# DRV8701.net
KiCad netlist of a schematic drawn in EasyEDA Pro
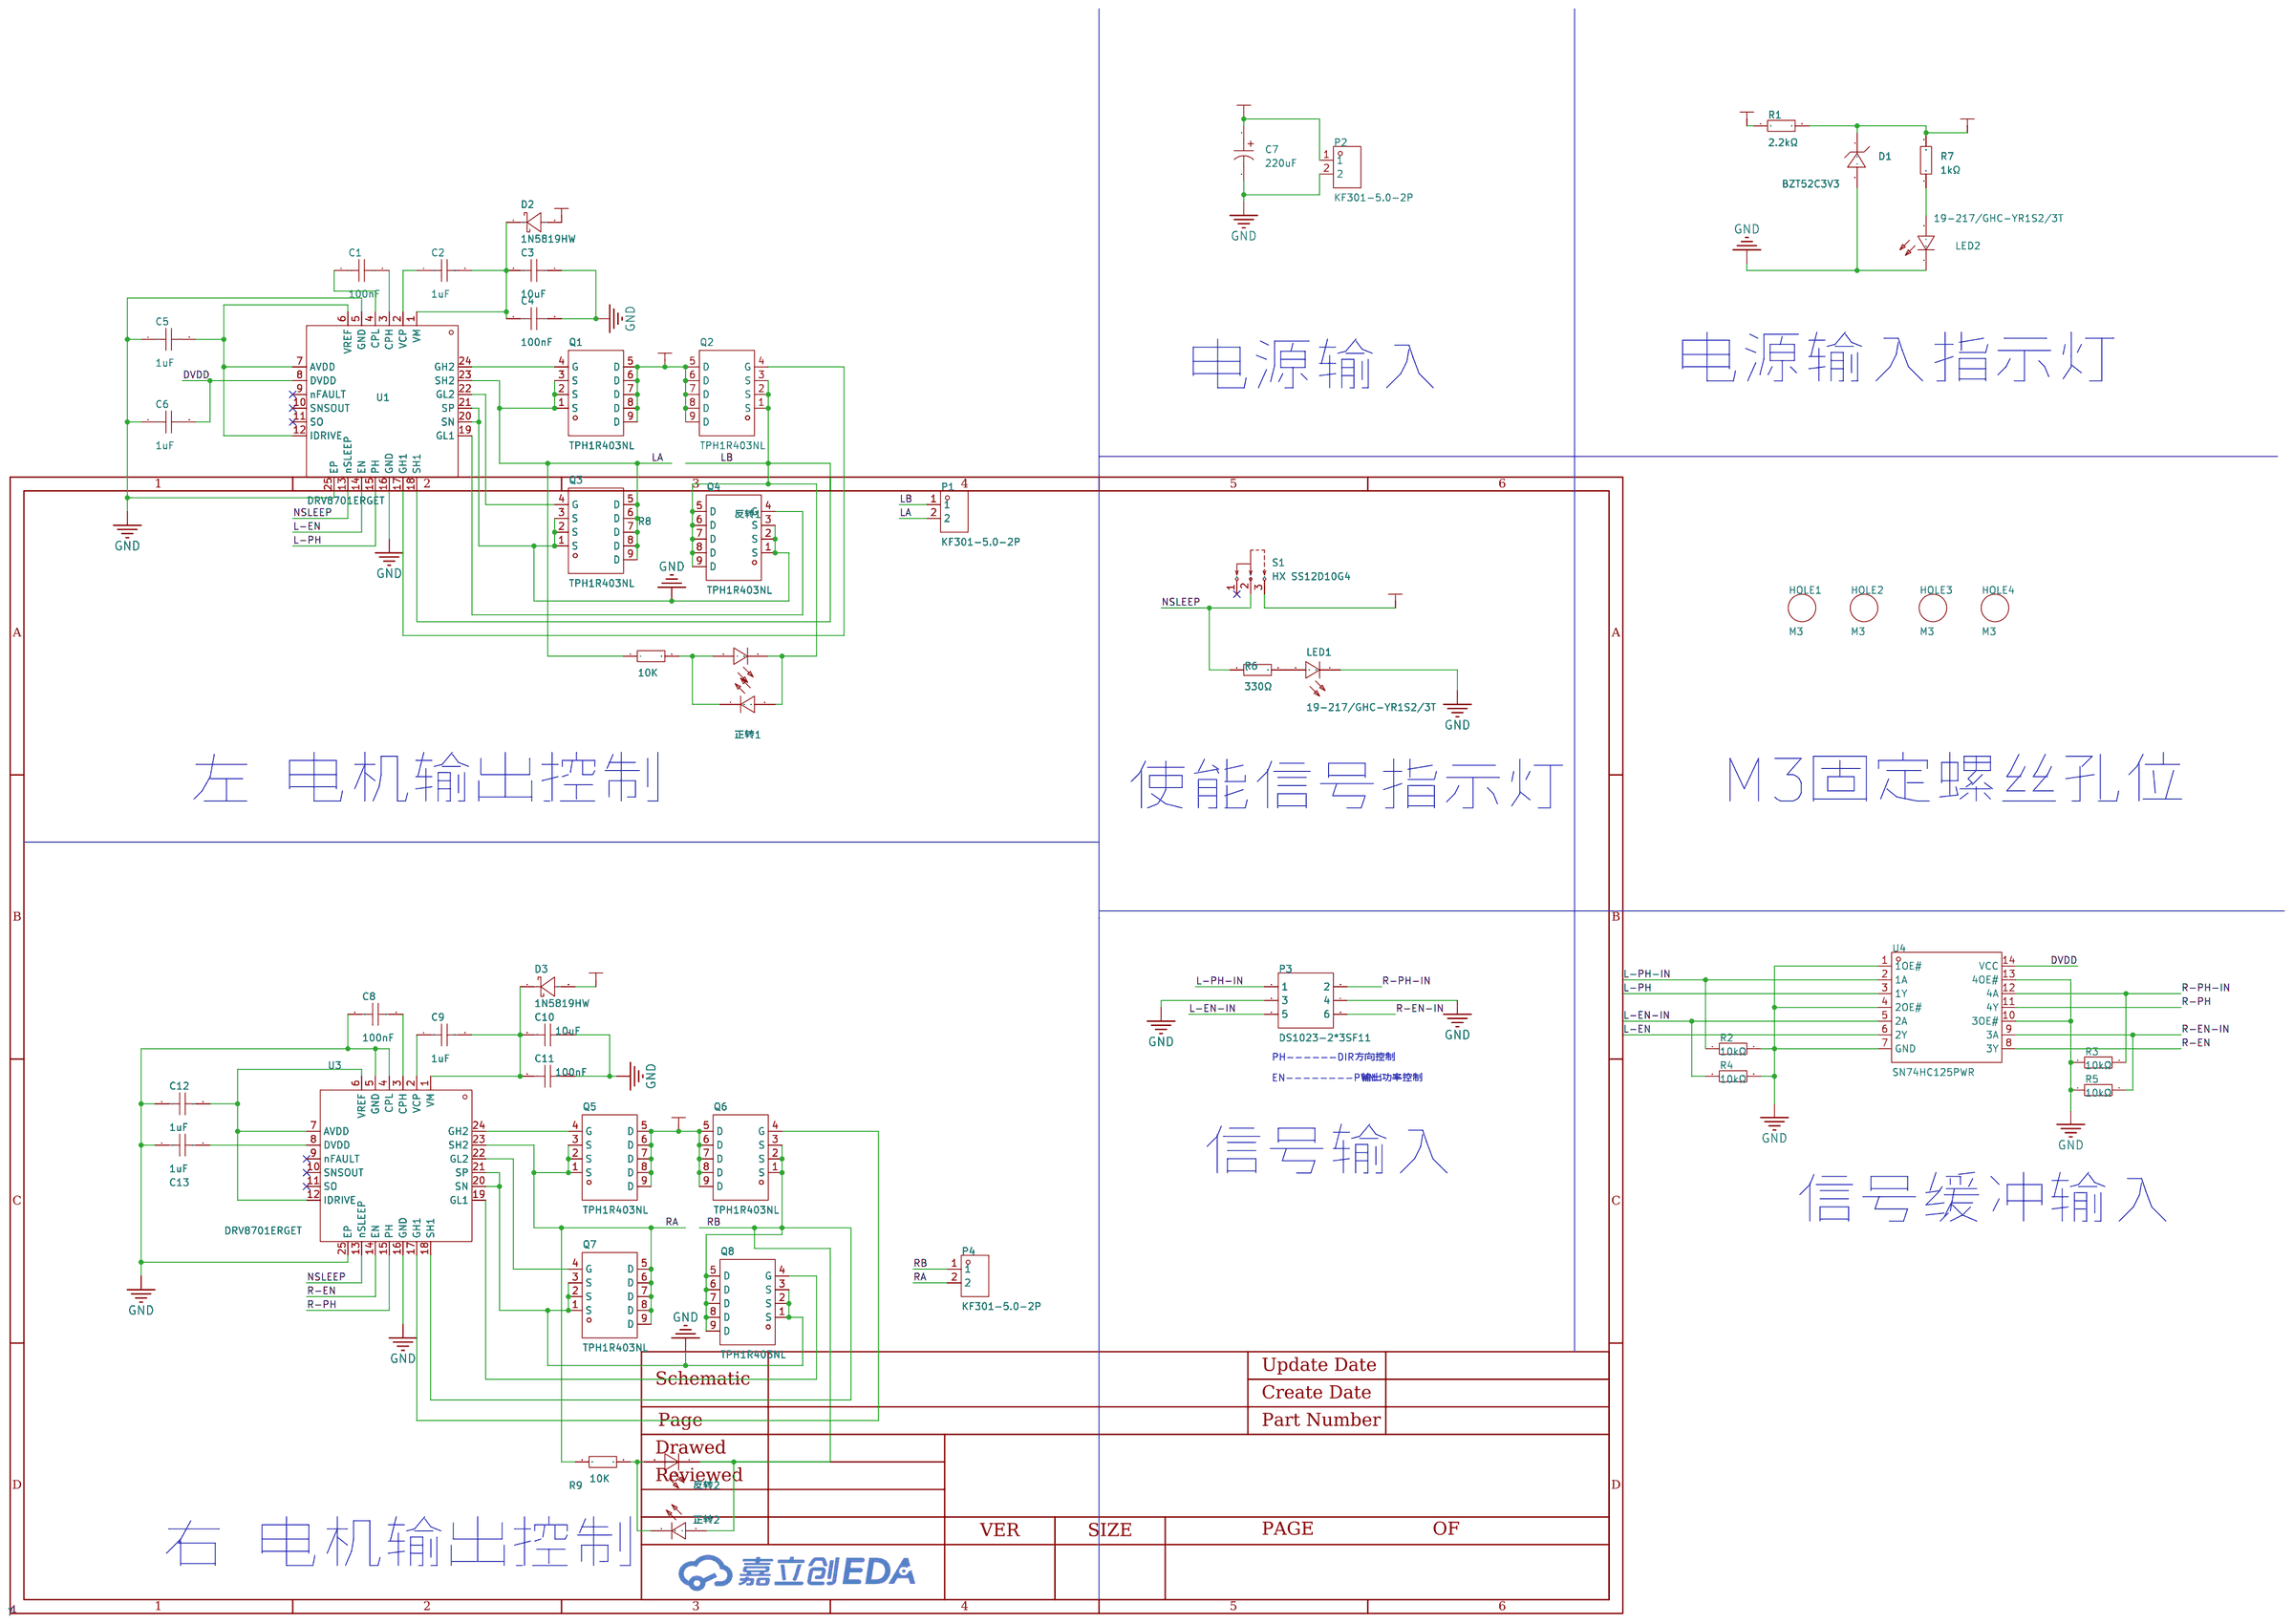
[diagram p0: schematic sheet]

(export (version "E")
  (design (tool "Eeschema 10.0.6"))
  (components
    (comp (ref "C1")
      (value "100nF")
      (footprint "easyedapro:C0603")
      (description "容值:100nF;精度:±10%;额定电压:16V;材质(温度系数):X7R;")
      (fields
        (field (name "Manufacturer Part") "LD03YC104KAB2A\\500")
        (field (name "Manufacturer") "Kyocera AVX")
      )
      (libsource (lib "easyedapro") (part "LD03YC104KAB2A{backslash}500"))
    )
    (comp (ref "C2")
      (value "1uF")
      (footprint "easyedapro:C0603")
      (fields
        (field (name "Manufacturer Part") "JMK063ABJ105MP-F")
        (field (name "Manufacturer") "TAIYO YUDEN(太诱)")
      )
      (libsource (lib "easyedapro") (part "YH-36P-贴片电容"))
    )
    (comp (ref "C3")
      (value "10uF")
      (footprint "easyedapro:C0603")
      (description "容值:10uF;精度:±20%;额定电压:16V;材质(温度系数):-;")
      (fields (field (name "Manufacturer") "SAMSUNG(三星)"))
      (libsource (lib "easyedapro") (part "10UF"))
    )
    (comp (ref "C4")
      (value "100nF")
      (footprint "easyedapro:C0603")
      (description "容值:100nF;精度:±10%;额定电压:16V;材质(温度系数):X7R;")
      (fields
        (field (name "Manufacturer Part") "LD03YC104KAB2A\\500")
        (field (name "Manufacturer") "Kyocera AVX")
      )
      (libsource (lib "easyedapro") (part "LD03YC104KAB2A{backslash}500"))
    )
    (comp (ref "C5")
      (value "1uF")
      (footprint "easyedapro:C0603")
      (fields
        (field (name "Manufacturer Part") "JMK063ABJ105MP-F")
        (field (name "Manufacturer") "TAIYO YUDEN(太诱)")
      )
      (libsource (lib "easyedapro") (part "YH-36P-贴片电容"))
    )
    (comp (ref "C6")
      (value "1uF")
      (footprint "easyedapro:C0603")
      (fields
        (field (name "Manufacturer Part") "JMK063ABJ105MP-F")
        (field (name "Manufacturer") "TAIYO YUDEN(太诱)")
      )
      (libsource (lib "easyedapro") (part "YH-36P-贴片电容"))
    )
    (comp (ref "C7")
      (value "220uF")
      (footprint "easyedapro:CAP-TH_BD6.3-P2.50-D0.5-FD")
      (fields
        (field (name "Manufacturer Part") "25YXJ220M6.3X11")
        (field (name "Manufacturer") "rubycon(红宝石)")
      )
      (libsource (lib "easyedapro") (part "220UF±20%25V 6.3*11 2.5MM"))
    )
    (comp (ref "C8")
      (value "100nF")
      (footprint "easyedapro:C0603")
      (description "容值:100nF;精度:±10%;额定电压:16V;材质(温度系数):X7R;")
      (fields
        (field (name "Manufacturer Part") "LD03YC104KAB2A\\500")
        (field (name "Manufacturer") "Kyocera AVX")
      )
      (libsource (lib "easyedapro") (part "LD03YC104KAB2A{backslash}500"))
    )
    (comp (ref "C9")
      (value "1uF")
      (footprint "easyedapro:C0603")
      (fields
        (field (name "Manufacturer Part") "JMK063ABJ105MP-F")
        (field (name "Manufacturer") "TAIYO YUDEN(太诱)")
      )
      (libsource (lib "easyedapro") (part "YH-36P-贴片电容"))
    )
    (comp (ref "C10")
      (value "10uF")
      (footprint "easyedapro:C0603")
      (description "容值:10uF;精度:±20%;额定电压:16V;材质(温度系数):-;")
      (fields (field (name "Manufacturer") "SAMSUNG(三星)"))
      (libsource (lib "easyedapro") (part "10UF"))
    )
    (comp (ref "C11")
      (value "100nF")
      (footprint "easyedapro:C0603")
      (description "容值:100nF;精度:±10%;额定电压:16V;材质(温度系数):X7R;")
      (fields
        (field (name "Manufacturer Part") "LD03YC104KAB2A\\500")
        (field (name "Manufacturer") "Kyocera AVX")
      )
      (libsource (lib "easyedapro") (part "LD03YC104KAB2A{backslash}500"))
    )
    (comp (ref "C12")
      (value "1uF")
      (footprint "easyedapro:C0603")
      (fields
        (field (name "Manufacturer Part") "JMK063ABJ105MP-F")
        (field (name "Manufacturer") "TAIYO YUDEN(太诱)")
      )
      (libsource (lib "easyedapro") (part "YH-36P-贴片电容"))
    )
    (comp (ref "C13")
      (value "1uF")
      (footprint "easyedapro:C0603")
      (fields
        (field (name "Manufacturer Part") "JMK063ABJ105MP-F")
        (field (name "Manufacturer") "TAIYO YUDEN(太诱)")
      )
      (libsource (lib "easyedapro") (part "YH-36P-贴片电容"))
    )
    (comp (ref "D1")
      (value "BZT52C3V3")
      (footprint "easyedapro:SOD-123_L2.8-W1.8-LS3.7-RD")
      (description "二极管配置:独立式;稳压值(标称值):3.3V;稳压值(范围):3.1V~3.5V;精度:-;功率:350mW;反向电流(Ir):5uA@1V;阻抗(Zzt):95Ω;")
      (fields (field (name "Manufacturer") "CJ(江苏长电/长晶)"))
      (libsource (lib "easyedapro") (part "BZT52C3V3_C2112"))
    )
    (comp (ref "D2")
      (value "1N5819HW")
      (footprint "easyedapro:SOD-123_L2.7-W1.6-LS3.7-RD-1")
      (description "二极管配置:-;直流反向耐压(Vr):40V;平均整流电流(Io):1A;正向压降(Vf):900mV@3A;反向电流(Ir):1mA@40V;")
      (fields (field (name "Manufacturer") "TECH PUBLIC(台舟)"))
      (libsource (lib "easyedapro") (part "1N5819HW"))
    )
    (comp (ref "D3")
      (value "1N5819HW")
      (footprint "easyedapro:SOD-123_L2.7-W1.6-LS3.7-RD-1")
      (description "二极管配置:-;直流反向耐压(Vr):40V;平均整流电流(Io):1A;正向压降(Vf):900mV@3A;反向电流(Ir):1mA@40V;")
      (fields (field (name "Manufacturer") "TECH PUBLIC(台舟)"))
      (libsource (lib "easyedapro") (part "1N5819HW"))
    )
    (comp (ref "HOLE1")
      (value "M3")
      (footprint "easyedapro:M3 5.4MM")
      (libsource (lib "easyedapro") (part "M3"))
    )
    (comp (ref "HOLE2")
      (value "M3")
      (footprint "easyedapro:M3 5.4MM")
      (libsource (lib "easyedapro") (part "M3"))
    )
    (comp (ref "HOLE3")
      (value "M3")
      (footprint "easyedapro:M3 5.4MM")
      (libsource (lib "easyedapro") (part "M3"))
    )
    (comp (ref "HOLE4")
      (value "M3")
      (footprint "easyedapro:M3 5.4MM")
      (libsource (lib "easyedapro") (part "M3"))
    )
    (comp (ref "LED1")
      (value "19-217/GHC-YR1S2/3T")
      (footprint "easyedapro:LED0603-RD")
      (description "发光颜色:翠绿;二极管配置:-;主波长:520nm~535nm;色温:-;功率:110mW;安装方式:-;")
      (fields (field (name "Manufacturer") "EVERLIGHT(亿光)"))
      (libsource (lib "easyedapro") (part "19-217/GHC-YR1S2/3T"))
    )
    (comp (ref "LED2")
      (value "19-217/GHC-YR1S2/3T")
      (footprint "easyedapro:LED0603-RD")
      (description "发光颜色:翠绿;二极管配置:-;主波长:520nm~535nm;色温:-;功率:110mW;安装方式:-;")
      (fields (field (name "Manufacturer") "EVERLIGHT(亿光)"))
      (libsource (lib "easyedapro") (part "19-217/GHC-YR1S2/3T"))
    )
    (comp (ref "P1")
      (value "KF301-5.0-2P")
      (footprint "easyedapro:CONN-TH_P5.00_KF301-5.0-2P")
      (fields (field (name "Manufacturer") "KEFA(科发)"))
      (libsource (lib "easyedapro") (part "KF301-5.0-2P"))
    )
    (comp (ref "P2")
      (value "KF301-5.0-2P")
      (footprint "easyedapro:CONN-TH_P5.00_KF301-5.0-2P")
      (fields (field (name "Manufacturer") "KEFA(科发)"))
      (libsource (lib "easyedapro") (part "KF301-5.0-2P"))
    )
    (comp (ref "P3")
      (value "DS1023-2*3SF11")
      (footprint "easyedapro:HDR-TH_6P-P2.54-V-F-R2-C3-S2.54")
      (description "排数:双排;总孔位数:6;间距:2.54mm;插孔结构:2x3P;行距:2.54mm;安装类型:直插;塑高:-;触头材质:-;触头镀层:-;")
      (fields (field (name "Manufacturer") "CONNFLY"))
      (libsource (lib "easyedapro") (part "Header-Female-2.54_2x3"))
    )
    (comp (ref "P4")
      (value "KF301-5.0-2P")
      (footprint "easyedapro:CONN-TH_P5.00_KF301-5.0-2P")
      (fields (field (name "Manufacturer") "KEFA(科发)"))
      (libsource (lib "easyedapro") (part "KF301-5.0-2P"))
    )
    (comp (ref "Q1")
      (value "TPH1R403NL")
      (footprint "easyedapro:DSOP-8_L5.0-W5.0-P1.27-LS6.0-BL-EP")
      (fields (field (name "Manufacturer") "TOSHIBA(东芝)"))
      (libsource (lib "easyedapro") (part "TPH1R403NL"))
    )
    (comp (ref "Q2")
      (value "TPH1R403NL")
      (footprint "easyedapro:DSOP-8_L5.0-W5.0-P1.27-LS6.0-BL-EP")
      (fields (field (name "Manufacturer") "TOSHIBA(东芝)"))
      (libsource (lib "easyedapro") (part "TPH1R403NL"))
    )
    (comp (ref "Q3")
      (value "TPH1R403NL")
      (footprint "easyedapro:DSOP-8_L5.0-W5.0-P1.27-LS6.0-BL-EP")
      (fields (field (name "Manufacturer") "TOSHIBA(东芝)"))
      (libsource (lib "easyedapro") (part "TPH1R403NL"))
    )
    (comp (ref "Q4")
      (value "TPH1R403NL")
      (footprint "easyedapro:DSOP-8_L5.0-W5.0-P1.27-LS6.0-BL-EP")
      (fields (field (name "Manufacturer") "TOSHIBA(东芝)"))
      (libsource (lib "easyedapro") (part "TPH1R403NL"))
    )
    (comp (ref "Q5")
      (value "TPH1R403NL")
      (footprint "easyedapro:DSOP-8_L5.0-W5.0-P1.27-LS6.0-BL-EP")
      (fields (field (name "Manufacturer") "TOSHIBA(东芝)"))
      (libsource (lib "easyedapro") (part "TPH1R403NL"))
    )
    (comp (ref "Q6")
      (value "TPH1R403NL")
      (footprint "easyedapro:DSOP-8_L5.0-W5.0-P1.27-LS6.0-BL-EP")
      (fields (field (name "Manufacturer") "TOSHIBA(东芝)"))
      (libsource (lib "easyedapro") (part "TPH1R403NL"))
    )
    (comp (ref "Q7")
      (value "TPH1R403NL")
      (footprint "easyedapro:DSOP-8_L5.0-W5.0-P1.27-LS6.0-BL-EP")
      (fields (field (name "Manufacturer") "TOSHIBA(东芝)"))
      (libsource (lib "easyedapro") (part "TPH1R403NL"))
    )
    (comp (ref "Q8")
      (value "TPH1R403NL")
      (footprint "easyedapro:DSOP-8_L5.0-W5.0-P1.27-LS6.0-BL-EP")
      (fields (field (name "Manufacturer") "TOSHIBA(东芝)"))
      (libsource (lib "easyedapro") (part "TPH1R403NL"))
    )
    (comp (ref "R1")
      (value "2.2kΩ")
      (footprint "easyedapro:R0805")
      (description "电阻类型:厚膜电阻;阻值:2.2kΩ;精度:±5%;功率:125mW;")
      (fields (field (name "Manufacturer Part") "RC0805JR-072K2L") (field (name "Manufacturer") "YAGEO(国巨)"))
      (libsource (lib "easyedapro") (part "RC0805JR-072K2L"))
    )
    (comp (ref "R2")
      (value "10kΩ")
      (footprint "easyedapro:R0603")
      (description "电阻类型:厚膜电阻;阻值:10kΩ;精度:±1%;功率:100mW;")
      (fields (field (name "Manufacturer Part") "AC0603FR-0710KL") (field (name "Manufacturer") "YAGEO(国巨)"))
      (libsource (lib "easyedapro") (part "AC0603FR-0710KL"))
    )
    (comp (ref "R3")
      (value "10kΩ")
      (footprint "easyedapro:R0603")
      (description "电阻类型:厚膜电阻;阻值:10kΩ;精度:±1%;功率:100mW;")
      (fields (field (name "Manufacturer Part") "AC0603FR-0710KL") (field (name "Manufacturer") "YAGEO(国巨)"))
      (libsource (lib "easyedapro") (part "AC0603FR-0710KL"))
    )
    (comp (ref "R4")
      (value "10kΩ")
      (footprint "easyedapro:R0603")
      (description "电阻类型:厚膜电阻;阻值:10kΩ;精度:±1%;功率:100mW;")
      (fields (field (name "Manufacturer Part") "AC0603FR-0710KL") (field (name "Manufacturer") "YAGEO(国巨)"))
      (libsource (lib "easyedapro") (part "AC0603FR-0710KL"))
    )
    (comp (ref "R5")
      (value "10kΩ")
      (footprint "easyedapro:R0603")
      (description "电阻类型:厚膜电阻;阻值:10kΩ;精度:±1%;功率:100mW;")
      (fields (field (name "Manufacturer Part") "AC0603FR-0710KL") (field (name "Manufacturer") "YAGEO(国巨)"))
      (libsource (lib "easyedapro") (part "AC0603FR-0710KL"))
    )
    (comp (ref "R6")
      (value "330Ω")
      (footprint "easyedapro:R0402")
      (description "电阻类型:厚膜电阻;阻值:330Ω;精度:±1%;功率:62.5mW;")
      (fields
        (field (name "Manufacturer Part") "0402WGF3300TCE")
        (field (name "Manufacturer") "UNI-ROYAL(厚声)")
      )
      (libsource (lib "easyedapro") (part "0402WGF3300TCE"))
    )
    (comp (ref "R7")
      (value "1kΩ")
      (footprint "easyedapro:R0603")
      (description "阻值:1kΩ;精度:±5%;功率:100mW;")
      (fields (field (name "Manufacturer Part") "ACD03K102JT") (field (name "Manufacturer") "FH(风华)"))
      (libsource (lib "easyedapro") (part "ACD03K102JT"))
    )
    (comp (ref "R8") (value "10K") (footprint "easyedapro:R0603") (libsource (lib "easyedapro") (part "电阻")))
    (comp (ref "R9") (value "10K") (footprint "easyedapro:R0603") (libsource (lib "easyedapro") (part "电阻")))
    (comp (ref "S1")
      (value "HX SS12D10G4")
      (footprint "easyedapro:SW-TH_SHOU-HAN_SS12D10G4")
      (fields (field (name "Manufacturer") "hanxia(韩下)"))
      (libsource (lib "easyedapro") (part "HX SS12D10G4"))
    )
    (comp (ref "U1")
      (value "DRV8701ERGET")
      (footprint "easyedapro:VQFN-24_L4.0-W4.0-P0.50-BL-EP2.5")
      (description "电源电压:0V~5.5V;输出电流:-;接口:并行;")
      (fields (field (name "Manufacturer") "TI(德州仪器)"))
      (libsource (lib "easyedapro") (part "DRV8701ERGET"))
    )
    (comp (ref "U3")
      (value "DRV8701ERGET")
      (footprint "easyedapro:VQFN-24_L4.0-W4.0-P0.50-BL-EP2.5")
      (description "电源电压:0V~5.5V;输出电流:-;接口:并行;")
      (fields (field (name "Manufacturer") "TI(德州仪器)"))
      (libsource (lib "easyedapro") (part "DRV8701ERGET"))
    )
    (comp (ref "U4")
      (value "SN74HC125PWR")
      (footprint "easyedapro:TSSOP-14_L5.0-W4.4-P0.65-LS6.5-BL")
      (description "类型:缓冲器，非反相;电源电压:2V~6V;输入类型:-;输出类型:三态;低电平输出电流(IOL):7.8mA;高电平输出电流(IOH):7.8mA;工作温度:-40°C~+85°C;")
      (fields (field (name "Manufacturer") "TI(德州仪器)"))
      (libsource (lib "easyedapro") (part "SN74HC125PWR"))
    )
    (comp (ref "反转1")
      (value "19-217/GHC-YR1S2/3T")
      (footprint "easyedapro:LED0603-RD")
      (description "发光颜色:翠绿;二极管配置:-;主波长:520nm~535nm;色温:-;功率:110mW;安装方式:-;")
      (fields (field (name "Manufacturer") "EVERLIGHT(亿光)"))
      (libsource (lib "easyedapro") (part "19-217/GHC-YR1S2/3T"))
    )
    (comp (ref "反转2")
      (value "19-217/GHC-YR1S2/3T")
      (footprint "easyedapro:LED0603-RD")
      (description "发光颜色:翠绿;二极管配置:-;主波长:520nm~535nm;色温:-;功率:110mW;安装方式:-;")
      (fields (field (name "Manufacturer") "EVERLIGHT(亿光)"))
      (libsource (lib "easyedapro") (part "19-217/GHC-YR1S2/3T"))
    )
    (comp (ref "正转1")
      (value "19-217/GHC-YR1S2/3T")
      (footprint "easyedapro:LED0603-RD")
      (description "发光颜色:翠绿;二极管配置:-;主波长:520nm~535nm;色温:-;功率:110mW;安装方式:-;")
      (fields (field (name "Manufacturer") "EVERLIGHT(亿光)"))
      (libsource (lib "easyedapro") (part "19-217/GHC-YR1S2/3T"))
    )
    (comp (ref "正转2")
      (value "19-217/GHC-YR1S2/3T")
      (footprint "easyedapro:LED0603-RD")
      (description "发光颜色:翠绿;二极管配置:-;主波长:520nm~535nm;色温:-;功率:110mW;安装方式:-;")
      (fields (field (name "Manufacturer") "EVERLIGHT(亿光)"))
      (libsource (lib "easyedapro") (part "19-217/GHC-YR1S2/3T"))
    )
  )
  (nets
    (net (code "1") (name "/DVDD") (class "Default")
      (node (ref "C6") (pin "2") (pinfunction "2_2") (pintype "input"))
      (node (ref "U1") (pin "8") (pinfunction "DVDD_8") (pintype "input"))
      (node (ref "U4") (pin "14") (pinfunction "VCC_14") (pintype "input"))
    )
    (net (code "2") (name "/L-EN") (class "Default")
      (node (ref "U1") (pin "14") (pinfunction "EN_14") (pintype "input"))
      (node (ref "U4") (pin "6") (pinfunction "2Y_6") (pintype "input"))
    )
    (net (code "3") (name "/L-EN-IN") (class "Default")
      (node (ref "P3") (pin "5") (pinfunction "5_5") (pintype "input"))
      (node (ref "R4") (pin "1") (pinfunction "1_1") (pintype "input"))
      (node (ref "U4") (pin "5") (pinfunction "2A_5") (pintype "input"))
    )
    (net (code "4") (name "/L-PH") (class "Default")
      (node (ref "U1") (pin "15") (pinfunction "PH_15") (pintype "input"))
      (node (ref "U4") (pin "3") (pinfunction "1Y_3") (pintype "input"))
    )
    (net (code "5") (name "/L-PH-IN") (class "Default")
      (node (ref "P3") (pin "1") (pinfunction "1_1") (pintype "input"))
      (node (ref "R2") (pin "1") (pinfunction "1_1") (pintype "input"))
      (node (ref "U4") (pin "2") (pinfunction "1A_2") (pintype "input"))
    )
    (net (code "6") (name "/LA") (class "Default")
      (node (ref "P1") (pin "2") (pinfunction "2_2") (pintype "input"))
      (node (ref "Q1") (pin "1") (pinfunction "S_1") (pintype "input"))
      (node (ref "Q1") (pin "2") (pinfunction "S_2") (pintype "input"))
      (node (ref "Q1") (pin "3") (pinfunction "S_3") (pintype "input"))
      (node (ref "Q3") (pin "5") (pinfunction "D_5") (pintype "input"))
      (node (ref "Q3") (pin "6") (pinfunction "D_6") (pintype "input"))
      (node (ref "Q3") (pin "7") (pinfunction "D_7") (pintype "input"))
      (node (ref "Q3") (pin "8") (pinfunction "D_8") (pintype "input"))
      (node (ref "Q3") (pin "9") (pinfunction "D_9") (pintype "input"))
      (node (ref "R8") (pin "1") (pinfunction "1_1") (pintype "input"))
      (node (ref "U1") (pin "23") (pinfunction "SH2_23") (pintype "input"))
    )
    (net (code "7") (name "/LB") (class "Default")
      (node (ref "P1") (pin "1") (pinfunction "1_1") (pintype "input"))
      (node (ref "Q2") (pin "1") (pinfunction "S_1") (pintype "input"))
      (node (ref "Q2") (pin "2") (pinfunction "S_2") (pintype "input"))
      (node (ref "Q2") (pin "3") (pinfunction "S_3") (pintype "input"))
      (node (ref "Q4") (pin "5") (pinfunction "D_5") (pintype "input"))
      (node (ref "Q4") (pin "6") (pinfunction "D_6") (pintype "input"))
      (node (ref "Q4") (pin "7") (pinfunction "D_7") (pintype "input"))
      (node (ref "Q4") (pin "8") (pinfunction "D_8") (pintype "input"))
      (node (ref "Q4") (pin "9") (pinfunction "D_9") (pintype "input"))
      (node (ref "U1") (pin "18") (pinfunction "SH1_18") (pintype "input"))
      (node (ref "反转1") (pin "1") (pinfunction "C_1") (pintype "input"))
      (node (ref "正转1") (pin "2") (pinfunction "A_2") (pintype "input"))
    )
    (net (code "8") (name "/NSLEEP") (class "Default")
      (node (ref "R6") (pin "1") (pinfunction "1_1") (pintype "input"))
      (node (ref "S1") (pin "2") (pinfunction "2_2") (pintype "input"))
      (node (ref "U1") (pin "13") (pinfunction "nSLEEP_13") (pintype "input"))
      (node (ref "U3") (pin "13") (pinfunction "nSLEEP_13") (pintype "input"))
    )
    (net (code "9") (name "/R-EN") (class "Default")
      (node (ref "U3") (pin "14") (pinfunction "EN_14") (pintype "input"))
      (node (ref "U4") (pin "8") (pinfunction "3Y_8") (pintype "input"))
    )
    (net (code "10") (name "/R-EN-IN") (class "Default")
      (node (ref "P3") (pin "6") (pinfunction "6_6") (pintype "input"))
      (node (ref "R5") (pin "2") (pinfunction "2_2") (pintype "input"))
      (node (ref "U4") (pin "9") (pinfunction "3A_9") (pintype "input"))
    )
    (net (code "11") (name "/R-PH") (class "Default")
      (node (ref "U3") (pin "15") (pinfunction "PH_15") (pintype "input"))
      (node (ref "U4") (pin "11") (pinfunction "4Y_11") (pintype "input"))
    )
    (net (code "12") (name "/R-PH-IN") (class "Default")
      (node (ref "P3") (pin "2") (pinfunction "2_2") (pintype "input"))
      (node (ref "R3") (pin "2") (pinfunction "2_2") (pintype "input"))
      (node (ref "U4") (pin "12") (pinfunction "4A_12") (pintype "input"))
    )
    (net (code "13") (name "/RA") (class "Default")
      (node (ref "P4") (pin "2") (pinfunction "2_2") (pintype "input"))
      (node (ref "Q5") (pin "1") (pinfunction "S_1") (pintype "input"))
      (node (ref "Q5") (pin "2") (pinfunction "S_2") (pintype "input"))
      (node (ref "Q5") (pin "3") (pinfunction "S_3") (pintype "input"))
      (node (ref "Q7") (pin "5") (pinfunction "D_5") (pintype "input"))
      (node (ref "Q7") (pin "6") (pinfunction "D_6") (pintype "input"))
      (node (ref "Q7") (pin "7") (pinfunction "D_7") (pintype "input"))
      (node (ref "Q7") (pin "8") (pinfunction "D_8") (pintype "input"))
      (node (ref "Q7") (pin "9") (pinfunction "D_9") (pintype "input"))
      (node (ref "R9") (pin "1") (pinfunction "1_1") (pintype "input"))
      (node (ref "U3") (pin "23") (pinfunction "SH2_23") (pintype "input"))
    )
    (net (code "14") (name "/RB") (class "Default")
      (node (ref "P4") (pin "1") (pinfunction "1_1") (pintype "input"))
      (node (ref "Q6") (pin "1") (pinfunction "S_1") (pintype "input"))
      (node (ref "Q6") (pin "2") (pinfunction "S_2") (pintype "input"))
      (node (ref "Q6") (pin "3") (pinfunction "S_3") (pintype "input"))
      (node (ref "Q8") (pin "5") (pinfunction "D_5") (pintype "input"))
      (node (ref "Q8") (pin "6") (pinfunction "D_6") (pintype "input"))
      (node (ref "Q8") (pin "7") (pinfunction "D_7") (pintype "input"))
      (node (ref "Q8") (pin "8") (pinfunction "D_8") (pintype "input"))
      (node (ref "Q8") (pin "9") (pinfunction "D_9") (pintype "input"))
      (node (ref "U3") (pin "18") (pinfunction "SH1_18") (pintype "input"))
      (node (ref "反转2") (pin "1") (pinfunction "C_1") (pintype "input"))
      (node (ref "正转2") (pin "2") (pinfunction "A_2") (pintype "input"))
    )
    (net (code "15") (name "3V3") (class "Default")
      (node (ref "D1") (pin "1") (pinfunction "K_1") (pintype "input"))
      (node (ref "R1") (pin "2") (pinfunction "2_2") (pintype "input"))
      (node (ref "R7") (pin "2") (pinfunction "2_2") (pintype "input"))
      (node (ref "S1") (pin "3") (pinfunction "3_3") (pintype "input"))
    )
    (net (code "16") (name "GND") (class "Default")
      (node (ref "C10") (pin "1") (pinfunction "1_1") (pintype "input"))
      (node (ref "C11") (pin "2") (pinfunction "2_2") (pintype "input"))
      (node (ref "C12") (pin "1") (pinfunction "1_1") (pintype "input"))
      (node (ref "C13") (pin "1") (pinfunction "1_1") (pintype "input"))
      (node (ref "C3") (pin "1") (pinfunction "1_1") (pintype "input"))
      (node (ref "C4") (pin "2") (pinfunction "2_2") (pintype "input"))
      (node (ref "C5") (pin "1") (pinfunction "1_1") (pintype "input"))
      (node (ref "C6") (pin "1") (pinfunction "1_1") (pintype "input"))
      (node (ref "C7") (pin "2") (pinfunction "2_2") (pintype "input"))
      (node (ref "C8") (pin "1") (pinfunction "1_1") (pintype "input"))
      (node (ref "D1") (pin "2") (pinfunction "A_2") (pintype "input"))
      (node (ref "LED1") (pin "1") (pinfunction "C_1") (pintype "input"))
      (node (ref "LED2") (pin "1") (pinfunction "C_1") (pintype "input"))
      (node (ref "P2") (pin "2") (pinfunction "2_2") (pintype "input"))
      (node (ref "P3") (pin "3") (pinfunction "3_3") (pintype "input"))
      (node (ref "P3") (pin "4") (pinfunction "4_4") (pintype "input"))
      (node (ref "Q3") (pin "1") (pinfunction "S_1") (pintype "input"))
      (node (ref "Q3") (pin "2") (pinfunction "S_2") (pintype "input"))
      (node (ref "Q3") (pin "3") (pinfunction "S_3") (pintype "input"))
      (node (ref "Q4") (pin "1") (pinfunction "S_1") (pintype "input"))
      (node (ref "Q4") (pin "2") (pinfunction "S_2") (pintype "input"))
      (node (ref "Q4") (pin "3") (pinfunction "S_3") (pintype "input"))
      (node (ref "Q7") (pin "1") (pinfunction "S_1") (pintype "input"))
      (node (ref "Q7") (pin "2") (pinfunction "S_2") (pintype "input"))
      (node (ref "Q7") (pin "3") (pinfunction "S_3") (pintype "input"))
      (node (ref "Q8") (pin "1") (pinfunction "S_1") (pintype "input"))
      (node (ref "Q8") (pin "2") (pinfunction "S_2") (pintype "input"))
      (node (ref "Q8") (pin "3") (pinfunction "S_3") (pintype "input"))
      (node (ref "R2") (pin "2") (pinfunction "2_2") (pintype "input"))
      (node (ref "R3") (pin "1") (pinfunction "1_1") (pintype "input"))
      (node (ref "R4") (pin "2") (pinfunction "2_2") (pintype "input"))
      (node (ref "R5") (pin "1") (pinfunction "1_1") (pintype "input"))
      (node (ref "U1") (pin "16") (pinfunction "GND_16") (pintype "input"))
      (node (ref "U1") (pin "20") (pinfunction "SN_20") (pintype "input"))
      (node (ref "U1") (pin "21") (pinfunction "SP_21") (pintype "input"))
      (node (ref "U1") (pin "25") (pinfunction "EP_25") (pintype "input"))
      (node (ref "U1") (pin "5") (pinfunction "GND_5") (pintype "input"))
      (node (ref "U3") (pin "16") (pinfunction "GND_16") (pintype "input"))
      (node (ref "U3") (pin "20") (pinfunction "SN_20") (pintype "input"))
      (node (ref "U3") (pin "21") (pinfunction "SP_21") (pintype "input"))
      (node (ref "U3") (pin "25") (pinfunction "EP_25") (pintype "input"))
      (node (ref "U3") (pin "4") (pinfunction "CPL_4") (pintype "input"))
      (node (ref "U3") (pin "5") (pinfunction "GND_5") (pintype "input"))
      (node (ref "U4") (pin "1") (pinfunction "1OE#_1") (pintype "input"))
      (node (ref "U4") (pin "10") (pinfunction "3OE#_10") (pintype "input"))
      (node (ref "U4") (pin "13") (pinfunction "4OE#_13") (pintype "input"))
      (node (ref "U4") (pin "4") (pinfunction "2OE#_4") (pintype "input"))
      (node (ref "U4") (pin "7") (pinfunction "GND_7") (pintype "input"))
    )
    (net (code "17") (name "Net-(D2-K)") (class "Default")
      (node (ref "C2") (pin "2") (pinfunction "2_2") (pintype "input"))
      (node (ref "C3") (pin "2") (pinfunction "2_2") (pintype "input"))
      (node (ref "C4") (pin "1") (pinfunction "1_1") (pintype "input"))
      (node (ref "D2") (pin "1") (pinfunction "K_1") (pintype "input"))
      (node (ref "U1") (pin "1") (pinfunction "VM_1") (pintype "input"))
    )
    (net (code "18") (name "Net-(D3-K)") (class "Default")
      (node (ref "C10") (pin "2") (pinfunction "2_2") (pintype "input"))
      (node (ref "C11") (pin "1") (pinfunction "1_1") (pintype "input"))
      (node (ref "C9") (pin "2") (pinfunction "2_2") (pintype "input"))
      (node (ref "D3") (pin "1") (pinfunction "K_1") (pintype "input"))
      (node (ref "U3") (pin "1") (pinfunction "VM_1") (pintype "input"))
    )
    (net (code "19") (name "Net-(LED1-A)") (class "Default")
      (node (ref "LED1") (pin "2") (pinfunction "A_2") (pintype "input"))
      (node (ref "R6") (pin "2") (pinfunction "2_2") (pintype "input"))
    )
    (net (code "20") (name "Net-(LED2-A)") (class "Default")
      (node (ref "LED2") (pin "2") (pinfunction "A_2") (pintype "input"))
      (node (ref "R7") (pin "1") (pinfunction "1_1") (pintype "input"))
    )
    (net (code "21") (name "Net-(Q1-G)") (class "Default")
      (node (ref "Q1") (pin "4") (pinfunction "G_4") (pintype "input"))
      (node (ref "U1") (pin "24") (pinfunction "GH2_24") (pintype "input"))
    )
    (net (code "22") (name "Net-(Q2-G)") (class "Default")
      (node (ref "Q2") (pin "4") (pinfunction "G_4") (pintype "input"))
      (node (ref "U1") (pin "17") (pinfunction "GH1_17") (pintype "input"))
    )
    (net (code "23") (name "Net-(Q3-G)") (class "Default")
      (node (ref "Q3") (pin "4") (pinfunction "G_4") (pintype "input"))
      (node (ref "U1") (pin "22") (pinfunction "GL2_22") (pintype "input"))
    )
    (net (code "24") (name "Net-(Q4-G)") (class "Default")
      (node (ref "Q4") (pin "4") (pinfunction "G_4") (pintype "input"))
      (node (ref "U1") (pin "19") (pinfunction "GL1_19") (pintype "input"))
    )
    (net (code "25") (name "Net-(Q5-G)") (class "Default")
      (node (ref "Q5") (pin "4") (pinfunction "G_4") (pintype "input"))
      (node (ref "U3") (pin "24") (pinfunction "GH2_24") (pintype "input"))
    )
    (net (code "26") (name "Net-(Q6-G)") (class "Default")
      (node (ref "Q6") (pin "4") (pinfunction "G_4") (pintype "input"))
      (node (ref "U3") (pin "17") (pinfunction "GH1_17") (pintype "input"))
    )
    (net (code "27") (name "Net-(Q7-G)") (class "Default")
      (node (ref "Q7") (pin "4") (pinfunction "G_4") (pintype "input"))
      (node (ref "U3") (pin "22") (pinfunction "GL2_22") (pintype "input"))
    )
    (net (code "28") (name "Net-(Q8-G)") (class "Default")
      (node (ref "Q8") (pin "4") (pinfunction "G_4") (pintype "input"))
      (node (ref "U3") (pin "19") (pinfunction "GL1_19") (pintype "input"))
    )
    (net (code "29") (name "Net-(U1-AVDD)") (class "Default")
      (node (ref "C5") (pin "2") (pinfunction "2_2") (pintype "input"))
      (node (ref "U1") (pin "12") (pinfunction "IDRIVE_12") (pintype "input"))
      (node (ref "U1") (pin "6") (pinfunction "VREF_6") (pintype "input"))
      (node (ref "U1") (pin "7") (pinfunction "AVDD_7") (pintype "input"))
    )
    (net (code "30") (name "Net-(U1-CPH)") (class "Default")
      (node (ref "C1") (pin "2") (pinfunction "2_2") (pintype "input"))
      (node (ref "U1") (pin "3") (pinfunction "CPH_3") (pintype "input"))
    )
    (net (code "31") (name "Net-(U1-CPL)") (class "Default")
      (node (ref "C1") (pin "1") (pinfunction "1_1") (pintype "input"))
      (node (ref "U1") (pin "4") (pinfunction "CPL_4") (pintype "input"))
    )
    (net (code "32") (name "Net-(U1-VCP)") (class "Default")
      (node (ref "C2") (pin "1") (pinfunction "1_1") (pintype "input"))
      (node (ref "U1") (pin "2") (pinfunction "VCP_2") (pintype "input"))
    )
    (net (code "33") (name "Net-(U3-AVDD)") (class "Default")
      (node (ref "C12") (pin "2") (pinfunction "2_2") (pintype "input"))
      (node (ref "U3") (pin "12") (pinfunction "IDRIVE_12") (pintype "input"))
      (node (ref "U3") (pin "6") (pinfunction "VREF_6") (pintype "input"))
      (node (ref "U3") (pin "7") (pinfunction "AVDD_7") (pintype "input"))
    )
    (net (code "34") (name "Net-(U3-CPH)") (class "Default")
      (node (ref "C8") (pin "2") (pinfunction "2_2") (pintype "input"))
      (node (ref "U3") (pin "3") (pinfunction "CPH_3") (pintype "input"))
    )
    (net (code "35") (name "Net-(U3-DVDD)") (class "Default")
      (node (ref "C13") (pin "2") (pinfunction "2_2") (pintype "input"))
      (node (ref "U3") (pin "8") (pinfunction "DVDD_8") (pintype "input"))
    )
    (net (code "36") (name "Net-(U3-VCP)") (class "Default")
      (node (ref "C9") (pin "1") (pinfunction "1_1") (pintype "input"))
      (node (ref "U3") (pin "2") (pinfunction "VCP_2") (pintype "input"))
    )
    (net (code "37") (name "Net-(反转1-A)") (class "Default")
      (node (ref "R8") (pin "2") (pinfunction "2_2") (pintype "input"))
      (node (ref "反转1") (pin "2") (pinfunction "A_2") (pintype "input"))
      (node (ref "正转1") (pin "1") (pinfunction "C_1") (pintype "input"))
    )
    (net (code "38") (name "Net-(反转2-A)") (class "Default")
      (node (ref "R9") (pin "2") (pinfunction "2_2") (pintype "input"))
      (node (ref "反转2") (pin "2") (pinfunction "A_2") (pintype "input"))
      (node (ref "正转2") (pin "1") (pinfunction "C_1") (pintype "input"))
    )
    (net (code "39") (name "VM") (class "Default")
      (node (ref "C7") (pin "1") (pinfunction "1_1") (pintype "input"))
      (node (ref "D2") (pin "2") (pinfunction "A_2") (pintype "input"))
      (node (ref "D3") (pin "2") (pinfunction "A_2") (pintype "input"))
      (node (ref "P2") (pin "1") (pinfunction "1_1") (pintype "input"))
      (node (ref "Q1") (pin "5") (pinfunction "D_5") (pintype "input"))
      (node (ref "Q1") (pin "6") (pinfunction "D_6") (pintype "input"))
      (node (ref "Q1") (pin "7") (pinfunction "D_7") (pintype "input"))
      (node (ref "Q1") (pin "8") (pinfunction "D_8") (pintype "input"))
      (node (ref "Q1") (pin "9") (pinfunction "D_9") (pintype "input"))
      (node (ref "Q2") (pin "5") (pinfunction "D_5") (pintype "input"))
      (node (ref "Q2") (pin "6") (pinfunction "D_6") (pintype "input"))
      (node (ref "Q2") (pin "7") (pinfunction "D_7") (pintype "input"))
      (node (ref "Q2") (pin "8") (pinfunction "D_8") (pintype "input"))
      (node (ref "Q2") (pin "9") (pinfunction "D_9") (pintype "input"))
      (node (ref "Q5") (pin "5") (pinfunction "D_5") (pintype "input"))
      (node (ref "Q5") (pin "6") (pinfunction "D_6") (pintype "input"))
      (node (ref "Q5") (pin "7") (pinfunction "D_7") (pintype "input"))
      (node (ref "Q5") (pin "8") (pinfunction "D_8") (pintype "input"))
      (node (ref "Q5") (pin "9") (pinfunction "D_9") (pintype "input"))
      (node (ref "Q6") (pin "5") (pinfunction "D_5") (pintype "input"))
      (node (ref "Q6") (pin "6") (pinfunction "D_6") (pintype "input"))
      (node (ref "Q6") (pin "7") (pinfunction "D_7") (pintype "input"))
      (node (ref "Q6") (pin "8") (pinfunction "D_8") (pintype "input"))
      (node (ref "Q6") (pin "9") (pinfunction "D_9") (pintype "input"))
      (node (ref "R1") (pin "1") (pinfunction "1_1") (pintype "input"))
    )
    (net (code "40") (name "unconnected-(S1-Pad1)") (class "Default")
      (node (ref "S1") (pin "1") (pinfunction "1_1") (pintype "input+no_connect"))
    )
    (net (code "41") (name "unconnected-(U1-SNSOUT-Pad10)") (class "Default")
      (node (ref "U1") (pin "10") (pinfunction "SNSOUT_10") (pintype "input+no_connect"))
    )
    (net (code "42") (name "unconnected-(U1-SO-Pad11)") (class "Default")
      (node (ref "U1") (pin "11") (pinfunction "SO_11") (pintype "input+no_connect"))
    )
    (net (code "43") (name "unconnected-(U1-nFAULT-Pad9)") (class "Default")
      (node (ref "U1") (pin "9") (pinfunction "nFAULT_9") (pintype "input+no_connect"))
    )
    (net (code "44") (name "unconnected-(U3-SNSOUT-Pad10)") (class "Default")
      (node (ref "U3") (pin "10") (pinfunction "SNSOUT_10") (pintype "input+no_connect"))
    )
    (net (code "45") (name "unconnected-(U3-SO-Pad11)") (class "Default")
      (node (ref "U3") (pin "11") (pinfunction "SO_11") (pintype "input+no_connect"))
    )
    (net (code "46") (name "unconnected-(U3-nFAULT-Pad9)") (class "Default")
      (node (ref "U3") (pin "9") (pinfunction "nFAULT_9") (pintype "input+no_connect"))
    )
  )
)
